# Kondensator-Lademodul.net
KiCad netlist of a schematic drawn in EAGLE
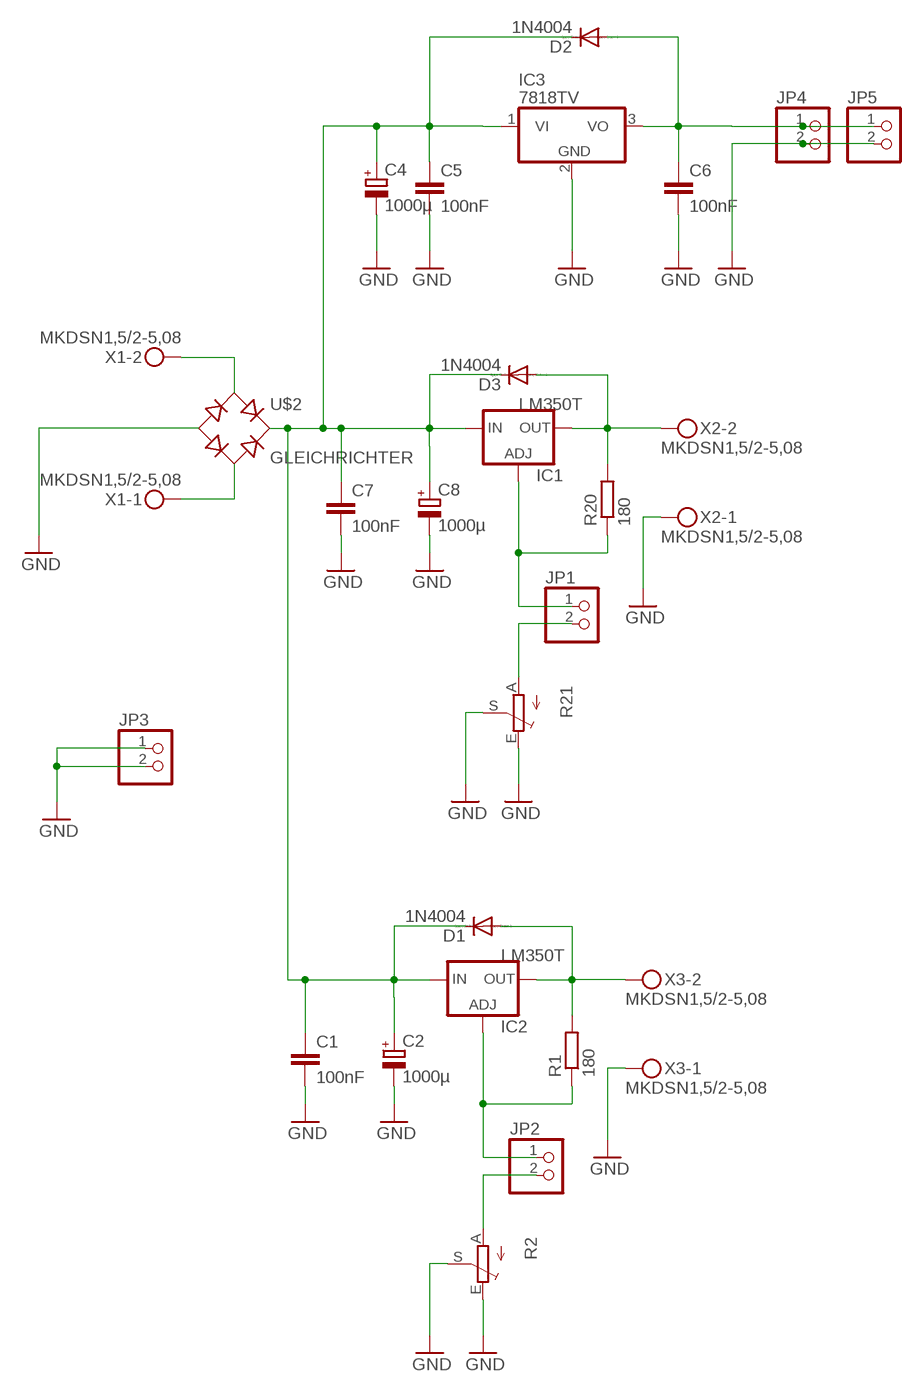
[diagram p0: schematic, sheet 1]

(export (version "E")
  (design (tool "Eeschema 10.0.6"))
  (components
    (comp (ref "C1")
      (value "100nF")
      (footprint "eagle-import:C0805")
      (libsource (lib "eagle-import") (part "C-EUC0805"))
    )
    (comp (ref "C2")
      (value "1000µ")
      (footprint "eagle-import:E5-13")
      (libsource (lib "eagle-import") (part "CPOL-EUE5-13"))
    )
    (comp (ref "C4")
      (value "1000µ")
      (footprint "eagle-import:E5-13")
      (libsource (lib "eagle-import") (part "CPOL-EUE5-13"))
    )
    (comp (ref "C5")
      (value "100nF")
      (footprint "eagle-import:C0805")
      (libsource (lib "eagle-import") (part "C-EUC0805"))
    )
    (comp (ref "C6")
      (value "100nF")
      (footprint "eagle-import:C0805")
      (libsource (lib "eagle-import") (part "C-EUC0805"))
    )
    (comp (ref "C7")
      (value "100nF")
      (footprint "eagle-import:C0805")
      (libsource (lib "eagle-import") (part "C-EUC0805"))
    )
    (comp (ref "C8")
      (value "1000µ")
      (footprint "eagle-import:E5-13")
      (libsource (lib "eagle-import") (part "CPOL-EUE5-13"))
    )
    (comp (ref "D1")
      (value "1N4004")
      (footprint "eagle-import:DO41-10")
      (libsource (lib "eagle-import") (part "1N4004"))
    )
    (comp (ref "D2")
      (value "1N4004")
      (footprint "eagle-import:DO41-10")
      (libsource (lib "eagle-import") (part "1N4004"))
    )
    (comp (ref "D3")
      (value "1N4004")
      (footprint "eagle-import:DO41-10")
      (libsource (lib "eagle-import") (part "1N4004"))
    )
    (comp (ref "IC1")
      (value "LM317TS")
      (footprint "eagle-import:317TS")
      (libsource (lib "eagle-import") (part "LM317TS"))
    )
    (comp (ref "IC2")
      (value "LM317TS")
      (footprint "eagle-import:317TS")
      (libsource (lib "eagle-import") (part "LM317TS"))
    )
    (comp (ref "IC3")
      (value "7818TV")
      (footprint "eagle-import:TO220V")
      (libsource (lib "eagle-import") (part "78TV05"))
    )
    (comp (ref "JP1")
      (value "PINHD-1X2")
      (footprint "eagle-import:1X02")
      (libsource (lib "eagle-import") (part "PINHD-1X2"))
    )
    (comp (ref "JP2")
      (value "PINHD-1X2")
      (footprint "eagle-import:1X02")
      (libsource (lib "eagle-import") (part "PINHD-1X2"))
    )
    (comp (ref "JP3")
      (value "PINHD-1X2")
      (footprint "eagle-import:1X02")
      (libsource (lib "eagle-import") (part "PINHD-1X2"))
    )
    (comp (ref "JP4")
      (value "PINHD-1X2")
      (footprint "eagle-import:1X02")
      (libsource (lib "eagle-import") (part "PINHD-1X2"))
    )
    (comp (ref "JP5")
      (value "PINHD-1X2")
      (footprint "eagle-import:1X02")
      (libsource (lib "eagle-import") (part "PINHD-1X2"))
    )
    (comp (ref "R1")
      (value "180")
      (footprint "eagle-import:R1206")
      (libsource (lib "eagle-import") (part "R-EU_R1206"))
    )
    (comp (ref "R2")
      (value "TRIM_EU-PT10")
      (footprint "eagle-import:PT-10")
      (libsource (lib "eagle-import") (part "TRIM_EU-PT10"))
    )
    (comp (ref "R20")
      (value "180")
      (footprint "eagle-import:R1206")
      (libsource (lib "eagle-import") (part "R-EU_R1206"))
    )
    (comp (ref "R21")
      (value "TRIM_EU-PT10")
      (footprint "eagle-import:PT-10")
      (libsource (lib "eagle-import") (part "TRIM_EU-PT10"))
    )
    (comp (ref "U$2")
      (value "GLEICHRICHTER")
      (footprint "eagle-import:KBPC1")
      (libsource (lib "eagle-import") (part "GLEICHRICHTER"))
    )
    (comp (ref "X1")
      (value "MKDSN1,5/2-5,08")
      (footprint "eagle-import:MKDSN1,5_2-5,08")
      (libsource (lib "eagle-import") (part "MKDSN1,5/2-5,08"))
    )
    (comp (ref "X2")
      (value "MKDSN1,5/2-5,08")
      (footprint "eagle-import:MKDSN1,5_2-5,08")
      (libsource (lib "eagle-import") (part "MKDSN1,5/2-5,08"))
    )
    (comp (ref "X3")
      (value "MKDSN1,5/2-5,08")
      (footprint "eagle-import:MKDSN1,5_2-5,08")
      (libsource (lib "eagle-import") (part "MKDSN1,5/2-5,08"))
    )
  )
  (nets
    (net (code "1") (name "GND") (class "Default")
      (node (ref "C1") (pin "2") (pinfunction "2_2") (pintype "passive"))
      (node (ref "C2") (pin "-") (pinfunction "-_-") (pintype "passive"))
      (node (ref "C4") (pin "-") (pinfunction "-_-") (pintype "passive"))
      (node (ref "C5") (pin "2") (pinfunction "2_2") (pintype "passive"))
      (node (ref "C6") (pin "2") (pinfunction "2_2") (pintype "passive"))
      (node (ref "C7") (pin "2") (pinfunction "2_2") (pintype "passive"))
      (node (ref "C8") (pin "-") (pinfunction "-_-") (pintype "passive"))
      (node (ref "IC3") (pin "2") (pinfunction "GND_2") (pintype "passive"))
      (node (ref "JP3") (pin "1") (pinfunction "1_1") (pintype "passive"))
      (node (ref "JP3") (pin "2") (pinfunction "2_2") (pintype "passive"))
      (node (ref "JP4") (pin "2") (pinfunction "2_2") (pintype "passive"))
      (node (ref "JP5") (pin "2") (pinfunction "2_2") (pintype "passive"))
      (node (ref "R2") (pin "E") (pinfunction "E_E") (pintype "passive"))
      (node (ref "R2") (pin "S") (pinfunction "S_S") (pintype "passive"))
      (node (ref "R21") (pin "E") (pinfunction "E_E") (pintype "passive"))
      (node (ref "R21") (pin "S") (pinfunction "S_S") (pintype "passive"))
      (node (ref "U$2") (pin "-") (pinfunction "-_-") (pintype "passive"))
      (node (ref "X2") (pin "1") (pinfunction "KL_1") (pintype "passive"))
      (node (ref "X3") (pin "1") (pinfunction "KL_1") (pintype "passive"))
    )
    (net (code "2") (name "Net-(IC1-ADJ)") (class "Default")
      (node (ref "IC1") (pin "1") (pinfunction "ADJ_1") (pintype "input"))
      (node (ref "JP1") (pin "1") (pinfunction "1_1") (pintype "passive"))
      (node (ref "R20") (pin "1") (pinfunction "1_1") (pintype "passive"))
    )
    (net (code "3") (name "Net-(IC1-IN)") (class "Default")
      (node (ref "C1") (pin "1") (pinfunction "1_1") (pintype "passive"))
      (node (ref "C2") (pin "+") (pinfunction "+_+") (pintype "passive"))
      (node (ref "C4") (pin "+") (pinfunction "+_+") (pintype "passive"))
      (node (ref "C5") (pin "1") (pinfunction "1_1") (pintype "passive"))
      (node (ref "C7") (pin "1") (pinfunction "1_1") (pintype "passive"))
      (node (ref "C8") (pin "+") (pinfunction "+_+") (pintype "passive"))
      (node (ref "D1") (pin "C") (pinfunction "C_C") (pintype "passive"))
      (node (ref "D2") (pin "C") (pinfunction "C_C") (pintype "passive"))
      (node (ref "D3") (pin "C") (pinfunction "C_C") (pintype "passive"))
      (node (ref "IC1") (pin "3") (pinfunction "IN_3") (pintype "input"))
      (node (ref "IC2") (pin "3") (pinfunction "IN_3") (pintype "input"))
      (node (ref "IC3") (pin "1") (pinfunction "VI_1") (pintype "input"))
      (node (ref "U$2") (pin "+") (pinfunction "+_+") (pintype "passive"))
    )
    (net (code "4") (name "Net-(IC1-OUT)") (class "Default")
      (node (ref "D3") (pin "A") (pinfunction "A_A") (pintype "passive"))
      (node (ref "IC1") (pin "2") (pinfunction "OUT_2") (pintype "passive"))
      (node (ref "R20") (pin "2") (pinfunction "2_2") (pintype "passive"))
      (node (ref "X2") (pin "2") (pinfunction "KL_2") (pintype "passive"))
    )
    (net (code "5") (name "Net-(IC2-ADJ)") (class "Default")
      (node (ref "IC2") (pin "1") (pinfunction "ADJ_1") (pintype "input"))
      (node (ref "JP2") (pin "1") (pinfunction "1_1") (pintype "passive"))
      (node (ref "R1") (pin "1") (pinfunction "1_1") (pintype "passive"))
    )
    (net (code "6") (name "Net-(IC2-OUT)") (class "Default")
      (node (ref "D1") (pin "A") (pinfunction "A_A") (pintype "passive"))
      (node (ref "IC2") (pin "2") (pinfunction "OUT_2") (pintype "passive"))
      (node (ref "R1") (pin "2") (pinfunction "2_2") (pintype "passive"))
      (node (ref "X3") (pin "2") (pinfunction "KL_2") (pintype "passive"))
    )
    (net (code "7") (name "Net-(IC3-VO)") (class "Default")
      (node (ref "C6") (pin "1") (pinfunction "1_1") (pintype "passive"))
      (node (ref "D2") (pin "A") (pinfunction "A_A") (pintype "passive"))
      (node (ref "IC3") (pin "3") (pinfunction "VO_3") (pintype "passive"))
      (node (ref "JP4") (pin "1") (pinfunction "1_1") (pintype "passive"))
      (node (ref "JP5") (pin "1") (pinfunction "1_1") (pintype "passive"))
    )
    (net (code "8") (name "Net-(JP1-Pad2)") (class "Default")
      (node (ref "JP1") (pin "2") (pinfunction "2_2") (pintype "passive"))
      (node (ref "R21") (pin "A") (pinfunction "A_A") (pintype "passive"))
    )
    (net (code "9") (name "Net-(JP2-Pad2)") (class "Default")
      (node (ref "JP2") (pin "2") (pinfunction "2_2") (pintype "passive"))
      (node (ref "R2") (pin "A") (pinfunction "A_A") (pintype "passive"))
    )
    (net (code "10") (name "Net-(X1A-KL)") (class "Default")
      (node (ref "U$2") (pin "AC2") (pinfunction "AC2_AC2") (pintype "passive"))
      (node (ref "X1") (pin "1") (pinfunction "KL_1") (pintype "passive"))
    )
    (net (code "11") (name "Net-(X1B-KL)") (class "Default")
      (node (ref "U$2") (pin "AC1") (pinfunction "AC1_AC1") (pintype "passive"))
      (node (ref "X1") (pin "2") (pinfunction "KL_2") (pintype "passive"))
    )
  )
)
